# USB.net
KiCad netlist of a schematic drawn in Altium Designer
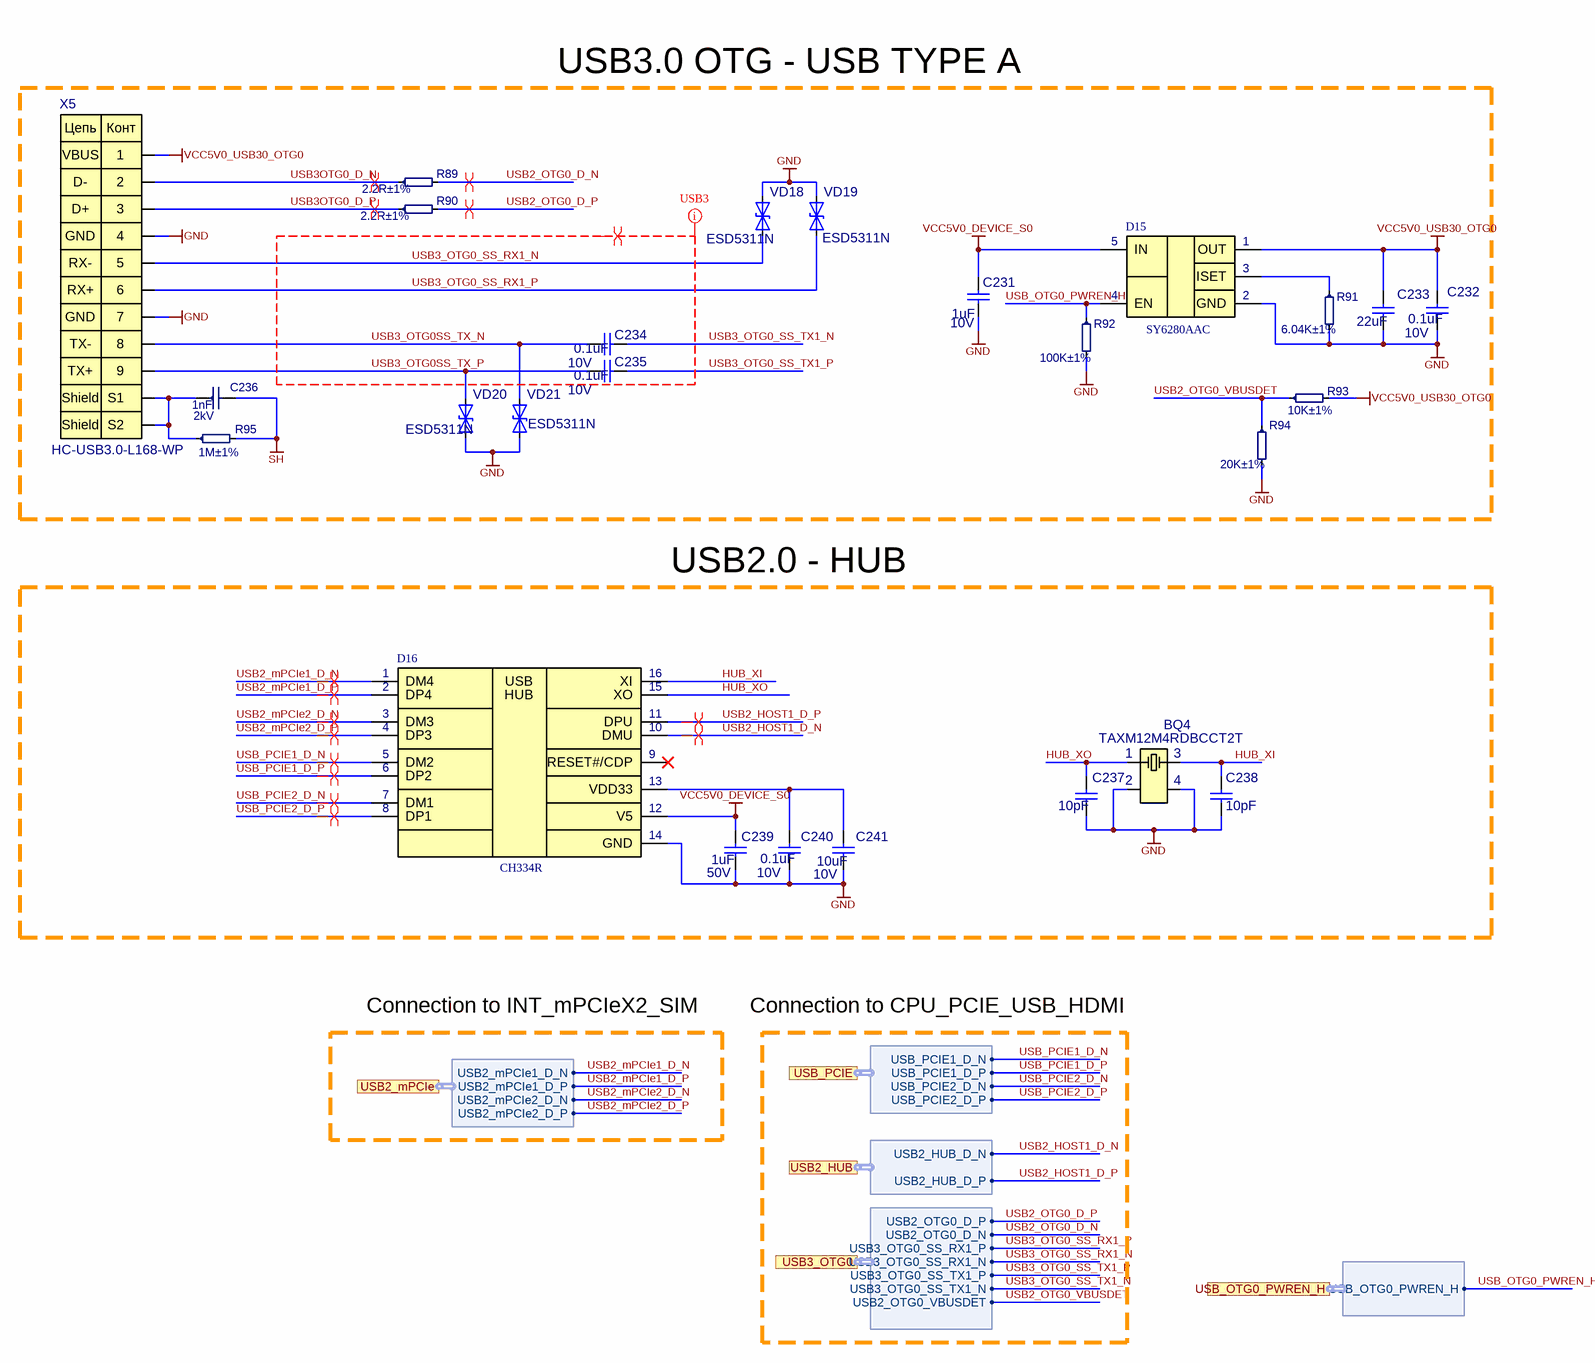
[diagram p0: USB.SchDoc]

(export (version "E")
  (design (tool "Eeschema 10.0.6"))
  (components
    (comp (ref "BQ4")
      (value "TAXM12M4RDBCCT2T")
      (footprint "XC32M4-12.000-F10NNFT")
      (description "12MHz 10pF ±10ppm SMD3225-4P")
      (fields (field (name "MANUFACTURER") "TAE"))
      (libsource (lib "LIB_RK") (part "XC32M4-12.000-F10NNFT"))
    )
    (comp (ref "C231")
      (value "1uF")
      (footprint "C0402")
      (fields
        (field (name "PART NUMBER") "0402-X5R-10V-1uF±10%")
        (field (name "VOLTAGE") "10V")
        (field (name "TOLERANCE") "10%")
        (field (name "MANUFACTURER") "Samsung")
      )
      (libsource (lib "ATB") (part "C"))
    )
    (comp (ref "C232")
      (value "0.1uF")
      (footprint "C0402")
      (fields
        (field (name "PART NUMBER") "0402-X5R-10V-0.1uF±10%")
        (field (name "VOLTAGE") "10V")
        (field (name "TOLERANCE") "10%")
        (field (name "MANUFACTURER") "Yageo")
      )
      (libsource (lib "ATB") (part "C"))
    )
    (comp (ref "C233")
      (value "22uF")
      (footprint "C0603")
      (fields
        (field (name "PART NUMBER") "0603-X5R-10V-22uF±20%")
        (field (name "VOLTAGE") "10V")
        (field (name "TOLERANCE") "20%")
      )
      (libsource (lib "ATB") (part "C"))
    )
    (comp (ref "C234")
      (value "0.1uF")
      (footprint "C0402")
      (fields
        (field (name "PART NUMBER") "0402-X5R-10V-0.1uF±10%")
        (field (name "VOLTAGE") "10V")
        (field (name "TOLERANCE") "10%")
        (field (name "MANUFACTURER") "Yageo")
      )
      (libsource (lib "") (part "C_1"))
    )
    (comp (ref "C235")
      (value "0.1uF")
      (footprint "C0402")
      (fields
        (field (name "PART NUMBER") "0402-X5R-10V-0.1uF±10%")
        (field (name "VOLTAGE") "10V")
        (field (name "TOLERANCE") "10%")
        (field (name "MANUFACTURER") "Yageo")
      )
      (libsource (lib "") (part "C_1"))
    )
    (comp (ref "C236")
      (value "1nF")
      (footprint "C1812")
      (fields
        (field (name "VOLTAGE") "2kV")
        (field (name "PART NUMBER") "1812-C0G-2kV-1nF±10%")
        (field (name "TOLERANCE") "5%")
        (field (name "MANUFACTURER") "FH")
      )
      (libsource (lib "") (part "C_2"))
    )
    (comp (ref "C237")
      (value "10pF")
      (footprint "C0402")
      (fields
        (field (name "PART NUMBER") "0402-NP0-50V-10pF±5%")
        (field (name "VOLTAGE") "50V")
        (field (name "TOLERANCE") "5%")
      )
      (libsource (lib "ATB") (part "C"))
    )
    (comp (ref "C238")
      (value "10pF")
      (footprint "C0402")
      (fields
        (field (name "PART NUMBER") "0402-NP0-50V-10pF±5%")
        (field (name "VOLTAGE") "50V")
        (field (name "TOLERANCE") "5%")
      )
      (libsource (lib "ATB") (part "C"))
    )
    (comp (ref "C239")
      (value "1uF")
      (footprint "C0603")
      (fields
        (field (name "PART NUMBER") "0603-X5R-50V-1uF±10%")
        (field (name "VOLTAGE") "50V")
        (field (name "TOLERANCE") "10%")
        (field (name "MANUFACTURER") "Yageo")
      )
      (libsource (lib "ATB") (part "C"))
    )
    (comp (ref "C240")
      (value "0.1uF")
      (footprint "C0402")
      (fields
        (field (name "PART NUMBER") "0402-X5R-10V-0.1uF±10%")
        (field (name "VOLTAGE") "10V")
        (field (name "TOLERANCE") "10%")
        (field (name "MANUFACTURER") "Yageo")
      )
      (libsource (lib "ATB") (part "C"))
    )
    (comp (ref "C241")
      (value "10uF")
      (footprint "C0402")
      (fields
        (field (name "PART NUMBER") "0402-X5R-10V-10uF±20%")
        (field (name "VOLTAGE") "10V")
        (field (name "TOLERANCE") "20%")
        (field (name "MANUFACTURER") "Murata Electronics")
      )
      (libsource (lib "ATB") (part "C"))
    )
    (comp (ref "D15")
      (value "SY6280AAC")
      (footprint "SY6280AAC")
      (description "Power Distribution Switches")
      (fields (field (name "MANUFACTURER") "Silergy Corp"))
      (libsource (lib "LIB_RK") (part "SY6280AAC"))
    )
    (comp (ref "D16")
      (value "CH334R")
      (footprint "CH334R")
      (description "4-port USB2.0 high-speed HUB controller")
      (fields (field (name "MANUFACTURER") "WCH"))
      (libsource (lib "LIB_RK") (part "CH334R"))
    )
    (comp (ref "R89")
      (value "2.2R±1%")
      (footprint "R0402")
      (fields
        (field (name "PART NUMBER") "0402-0.0625W-2.2R-100ppm±1%")
        (field (name "TOLERANCE") "1%")
        (field (name "MANUFACTURER") "Yageo")
      )
      (libsource (lib "ATB") (part "R"))
    )
    (comp (ref "R90")
      (value "2.2R±1%")
      (footprint "R0402")
      (fields
        (field (name "PART NUMBER") "0402-0.0625W-2.2R-100ppm±1%")
        (field (name "TOLERANCE") "1%")
        (field (name "MANUFACTURER") "Yageo")
      )
      (libsource (lib "ATB") (part "R"))
    )
    (comp (ref "R91")
      (value "6.04K±1%")
      (footprint "R0402")
      (fields
        (field (name "PART NUMBER") "0402-0.0625W-6.04K-100ppm±1%")
        (field (name "TOLERANCE") "1%")
        (field (name "MANUFACTURER") "Yageo")
      )
      (libsource (lib "ATB") (part "R"))
    )
    (comp (ref "R92")
      (value "100K±1%")
      (footprint "R0402")
      (description "Chip Resistor 0402 100kΩ ±1% 50V ±100ppm/℃ Thick Film")
      (fields (field (name "PART NUMBER") "0402-0.0625W-100K-100ppm±1%") (field (name "TOLERANCE") "1%"))
      (libsource (lib "ATB") (part "R"))
    )
    (comp (ref "R93")
      (value "10K±1%")
      (footprint "R0402")
      (description "Chip Resistor 0402 10kΩ ±1% 50V ±100ppm/℃ Thick Film")
      (fields (field (name "PART NUMBER") "0402-0.0625W-10K-100ppm±1%") (field (name "TOLERANCE") "1%"))
      (libsource (lib "ATB") (part "R"))
    )
    (comp (ref "R94")
      (value "20K±1%")
      (footprint "R0402")
      (description "Chip Resistor 0402 20kΩ ±1% 50V ±100ppm/℃ Thick Film")
      (fields (field (name "PART NUMBER") "0402-0.0625W-20K-100ppm±1%") (field (name "TOLERANCE") "1%"))
      (libsource (lib "ATB") (part "R"))
    )
    (comp (ref "R95")
      (value "1M±1%")
      (footprint "R1206")
      (description "Chip Resistor 1206 1MΩ ±1% 200V ±100ppm/℃ Thick Film")
      (fields (field (name "PART NUMBER") "1206-0.25W-1M-100ppm±1%") (field (name "TOLERANCE") "1%"))
      (libsource (lib "ATB") (part "R"))
    )
    (comp (ref "VD18")
      (value "ESD5311N")
      (footprint "ESD5311N")
      (description "1-Line, Bi-directional, Transient Voltage Suppressors.0.25pF.")
      (fields (field (name "MANUFACTURER") "UMW"))
      (libsource (lib "LIB_RK") (part "ESD5311N"))
    )
    (comp (ref "VD19")
      (value "ESD5311N")
      (footprint "ESD5311N")
      (description "1-Line, Bi-directional, Transient Voltage Suppressors.0.25pF.")
      (fields (field (name "MANUFACTURER") "UMW"))
      (libsource (lib "LIB_RK") (part "ESD5311N"))
    )
    (comp (ref "VD20")
      (value "ESD5311N")
      (footprint "ESD5311N")
      (description "1-Line, Bi-directional, Transient Voltage Suppressors.0.25pF.")
      (fields (field (name "MANUFACTURER") "UMW"))
      (libsource (lib "LIB_RK") (part "ESD5311N"))
    )
    (comp (ref "VD21")
      (value "ESD5311N")
      (footprint "ESD5311N")
      (description "1-Line, Bi-directional, Transient Voltage Suppressors.0.25pF.")
      (fields (field (name "MANUFACTURER") "UMW"))
      (libsource (lib "LIB_RK") (part "ESD5311N"))
    )
    (comp (ref "X5")
      (value "HC-USB3.0-L168-WP")
      (footprint "DS1095-05")
      (description "USB type A, USB 3.0, right angle")
      (fields (field (name "MANUFACTURER") "Hong Cheng"))
      (libsource (lib "ATB") (part "DS1095-05"))
    )
  )
  (nets
    (net (code "5") (name "/HUB_XI") (class "Default")
      (node (ref "BQ4") (pin "3") (pinfunction "3_3") (pintype "passive"))
      (node (ref "C238") (pin "2") (pinfunction "2_2") (pintype "passive"))
      (node (ref "D16") (pin "16") (pinfunction "XI_16") (pintype "passive"))
    )
    (net (code "6") (name "/HUB_XO") (class "Default")
      (node (ref "BQ4") (pin "1") (pinfunction "1_1") (pintype "passive"))
      (node (ref "C237") (pin "2") (pinfunction "2_2") (pintype "passive"))
      (node (ref "D16") (pin "15") (pinfunction "XO_15") (pintype "passive"))
    )
    (net (code "7") (name "/USB2_HOST1_D_N") (class "Default")
      (node (ref "D16") (pin "10") (pinfunction "DMU_10") (pintype "passive"))
    )
    (net (code "8") (name "/USB2_HOST1_D_P") (class "Default")
      (node (ref "D16") (pin "11") (pinfunction "DPU_11") (pintype "passive"))
    )
    (net (code "9") (name "/USB2_OTG0_D_N") (class "Default")
      (node (ref "R89") (pin "2") (pinfunction "2_2") (pintype "passive"))
    )
    (net (code "10") (name "/USB2_OTG0_D_P") (class "Default")
      (node (ref "R90") (pin "2") (pinfunction "2_2") (pintype "passive"))
    )
    (net (code "11") (name "/USB2_OTG0_VBUSDET") (class "Default")
      (node (ref "R93") (pin "1") (pinfunction "1_1") (pintype "passive"))
      (node (ref "R94") (pin "1") (pinfunction "1_1") (pintype "passive"))
    )
    (net (code "12") (name "/USB2_mPCIe1_D_N") (class "Default")
      (node (ref "D16") (pin "1") (pinfunction "DM4_1") (pintype "passive"))
    )
    (net (code "13") (name "/USB2_mPCIe1_D_P") (class "Default")
      (node (ref "D16") (pin "2") (pinfunction "DP4_2") (pintype "passive"))
    )
    (net (code "14") (name "/USB2_mPCIe2_D_N") (class "Default")
      (node (ref "D16") (pin "3") (pinfunction "DM3_3") (pintype "passive"))
    )
    (net (code "15") (name "/USB2_mPCIe2_D_P") (class "Default")
      (node (ref "D16") (pin "4") (pinfunction "DP3_4") (pintype "passive"))
    )
    (net (code "16") (name "/USB3OTG0_D_N") (class "Default")
      (node (ref "R89") (pin "1") (pinfunction "1_1") (pintype "passive"))
      (node (ref "X5") (pin "2") (pinfunction "2_2") (pintype "passive"))
    )
    (net (code "17") (name "/USB3OTG0_D_P") (class "Default")
      (node (ref "R90") (pin "1") (pinfunction "1_1") (pintype "passive"))
      (node (ref "X5") (pin "3") (pinfunction "3_3") (pintype "passive"))
    )
    (net (code "18") (name "/USB3_OTG0SS_TX_N") (class "Default")
      (node (ref "C234") (pin "2") (pinfunction "2_2") (pintype "passive"))
      (node (ref "VD21") (pin "2") (pinfunction "2_2") (pintype "passive"))
      (node (ref "X5") (pin "8") (pinfunction "8_8") (pintype "passive"))
    )
    (net (code "19") (name "/USB3_OTG0SS_TX_P") (class "Default")
      (node (ref "C235") (pin "2") (pinfunction "2_2") (pintype "passive"))
      (node (ref "VD20") (pin "2") (pinfunction "2_2") (pintype "passive"))
      (node (ref "X5") (pin "9") (pinfunction "9_9") (pintype "passive"))
    )
    (net (code "20") (name "/USB3_OTG0_SS_RX1_N") (class "Default")
      (node (ref "VD18") (pin "1") (pinfunction "1_1") (pintype "passive"))
      (node (ref "X5") (pin "5") (pinfunction "5_5") (pintype "passive"))
    )
    (net (code "21") (name "/USB3_OTG0_SS_RX1_P") (class "Default")
      (node (ref "VD19") (pin "1") (pinfunction "1_1") (pintype "passive"))
      (node (ref "X5") (pin "6") (pinfunction "6_6") (pintype "passive"))
    )
    (net (code "22") (name "/USB3_OTG0_SS_TX1_N") (class "Default")
      (node (ref "C234") (pin "1") (pinfunction "1_1") (pintype "passive"))
    )
    (net (code "23") (name "/USB3_OTG0_SS_TX1_P") (class "Default")
      (node (ref "C235") (pin "1") (pinfunction "1_1") (pintype "passive"))
    )
    (net (code "24") (name "/USB_OTG0_PWREN_H") (class "Default")
      (node (ref "D15") (pin "4") (pinfunction "EN_4") (pintype "passive"))
      (node (ref "R92") (pin "1") (pinfunction "1_1") (pintype "passive"))
    )
    (net (code "25") (name "/USB_PCIE1_D_N") (class "Default")
      (node (ref "D16") (pin "5") (pinfunction "DM2_5") (pintype "passive"))
    )
    (net (code "26") (name "/USB_PCIE1_D_P") (class "Default")
      (node (ref "D16") (pin "6") (pinfunction "DP2_6") (pintype "passive"))
    )
    (net (code "27") (name "/USB_PCIE2_D_N") (class "Default")
      (node (ref "D16") (pin "7") (pinfunction "DM1_7") (pintype "passive"))
    )
    (net (code "28") (name "/USB_PCIE2_D_P") (class "Default")
      (node (ref "D16") (pin "8") (pinfunction "DP1_8") (pintype "passive"))
    )
    (net (code "34") (name "GND") (class "Default")
      (node (ref "BQ4") (pin "2") (pinfunction "2_2") (pintype "passive"))
      (node (ref "BQ4") (pin "4") (pinfunction "4_4") (pintype "passive"))
      (node (ref "C231") (pin "1") (pinfunction "1_1") (pintype "passive"))
      (node (ref "C232") (pin "2") (pinfunction "2_2") (pintype "passive"))
      (node (ref "C233") (pin "1") (pinfunction "1_1") (pintype "passive"))
      (node (ref "C237") (pin "1") (pinfunction "1_1") (pintype "passive"))
      (node (ref "C238") (pin "1") (pinfunction "1_1") (pintype "passive"))
      (node (ref "C239") (pin "1") (pinfunction "1_1") (pintype "passive"))
      (node (ref "C240") (pin "2") (pinfunction "2_2") (pintype "passive"))
      (node (ref "C241") (pin "1") (pinfunction "1_1") (pintype "passive"))
      (node (ref "D15") (pin "2") (pinfunction "GND_2") (pintype "passive"))
      (node (ref "D16") (pin "14") (pinfunction "GND_14") (pintype "passive"))
      (node (ref "R91") (pin "2") (pinfunction "2_2") (pintype "passive"))
      (node (ref "R92") (pin "2") (pinfunction "2_2") (pintype "passive"))
      (node (ref "R94") (pin "2") (pinfunction "2_2") (pintype "passive"))
      (node (ref "VD18") (pin "2") (pinfunction "2_2") (pintype "passive"))
      (node (ref "VD19") (pin "2") (pinfunction "2_2") (pintype "passive"))
      (node (ref "VD20") (pin "1") (pinfunction "1_1") (pintype "passive"))
      (node (ref "VD21") (pin "1") (pinfunction "1_1") (pintype "passive"))
      (node (ref "X5") (pin "4") (pinfunction "4_4") (pintype "passive"))
      (node (ref "X5") (pin "7") (pinfunction "7_7") (pintype "passive"))
    )
    (net (code "35") (name "Net-(C236-Pad1)") (class "Default")
      (node (ref "C236") (pin "1") (pinfunction "1_1") (pintype "passive"))
      (node (ref "R95") (pin "1") (pinfunction "1_1") (pintype "passive"))
      (node (ref "X5") (pin "S1") (pinfunction "S1_S1") (pintype "passive"))
      (node (ref "X5") (pin "S2") (pinfunction "S2_S2") (pintype "passive"))
    )
    (net (code "36") (name "Net-(D15-ISET)") (class "Default")
      (node (ref "D15") (pin "3") (pinfunction "ISET_3") (pintype "passive"))
      (node (ref "R91") (pin "1") (pinfunction "1_1") (pintype "passive"))
    )
    (net (code "37") (name "Net-(D16-VDD33)") (class "Default")
      (node (ref "C240") (pin "1") (pinfunction "1_1") (pintype "passive"))
      (node (ref "C241") (pin "2") (pinfunction "2_2") (pintype "passive"))
      (node (ref "D16") (pin "13") (pinfunction "VDD33_13") (pintype "passive"))
    )
    (net (code "38") (name "SH") (class "Default")
      (node (ref "C236") (pin "2") (pinfunction "2_2") (pintype "passive"))
      (node (ref "R95") (pin "2") (pinfunction "2_2") (pintype "passive"))
    )
    (net (code "39") (name "VCC5V0_DEVICE_S0") (class "Default")
      (node (ref "C231") (pin "2") (pinfunction "2_2") (pintype "passive"))
      (node (ref "C239") (pin "2") (pinfunction "2_2") (pintype "passive"))
      (node (ref "D15") (pin "5") (pinfunction "IN_5") (pintype "passive"))
      (node (ref "D16") (pin "12") (pinfunction "V5_12") (pintype "passive"))
    )
    (net (code "40") (name "VCC5V0_USB30_OTG0") (class "Default")
      (node (ref "C232") (pin "1") (pinfunction "1_1") (pintype "passive"))
      (node (ref "C233") (pin "2") (pinfunction "2_2") (pintype "passive"))
      (node (ref "D15") (pin "1") (pinfunction "OUT_1") (pintype "passive"))
      (node (ref "R93") (pin "2") (pinfunction "2_2") (pintype "passive"))
      (node (ref "X5") (pin "1") (pinfunction "1_1") (pintype "passive"))
    )
    (net (code "41") (name "unconnected-(D16-RESET#{slash}CDP-Pad9)") (class "Default")
      (node (ref "D16") (pin "9") (pinfunction "RESET#/CDP_9") (pintype "passive+no_connect"))
    )
  )
)
